# TY_FC_13.net
KiCad netlist of a schematic drawn in EasyEDA Pro
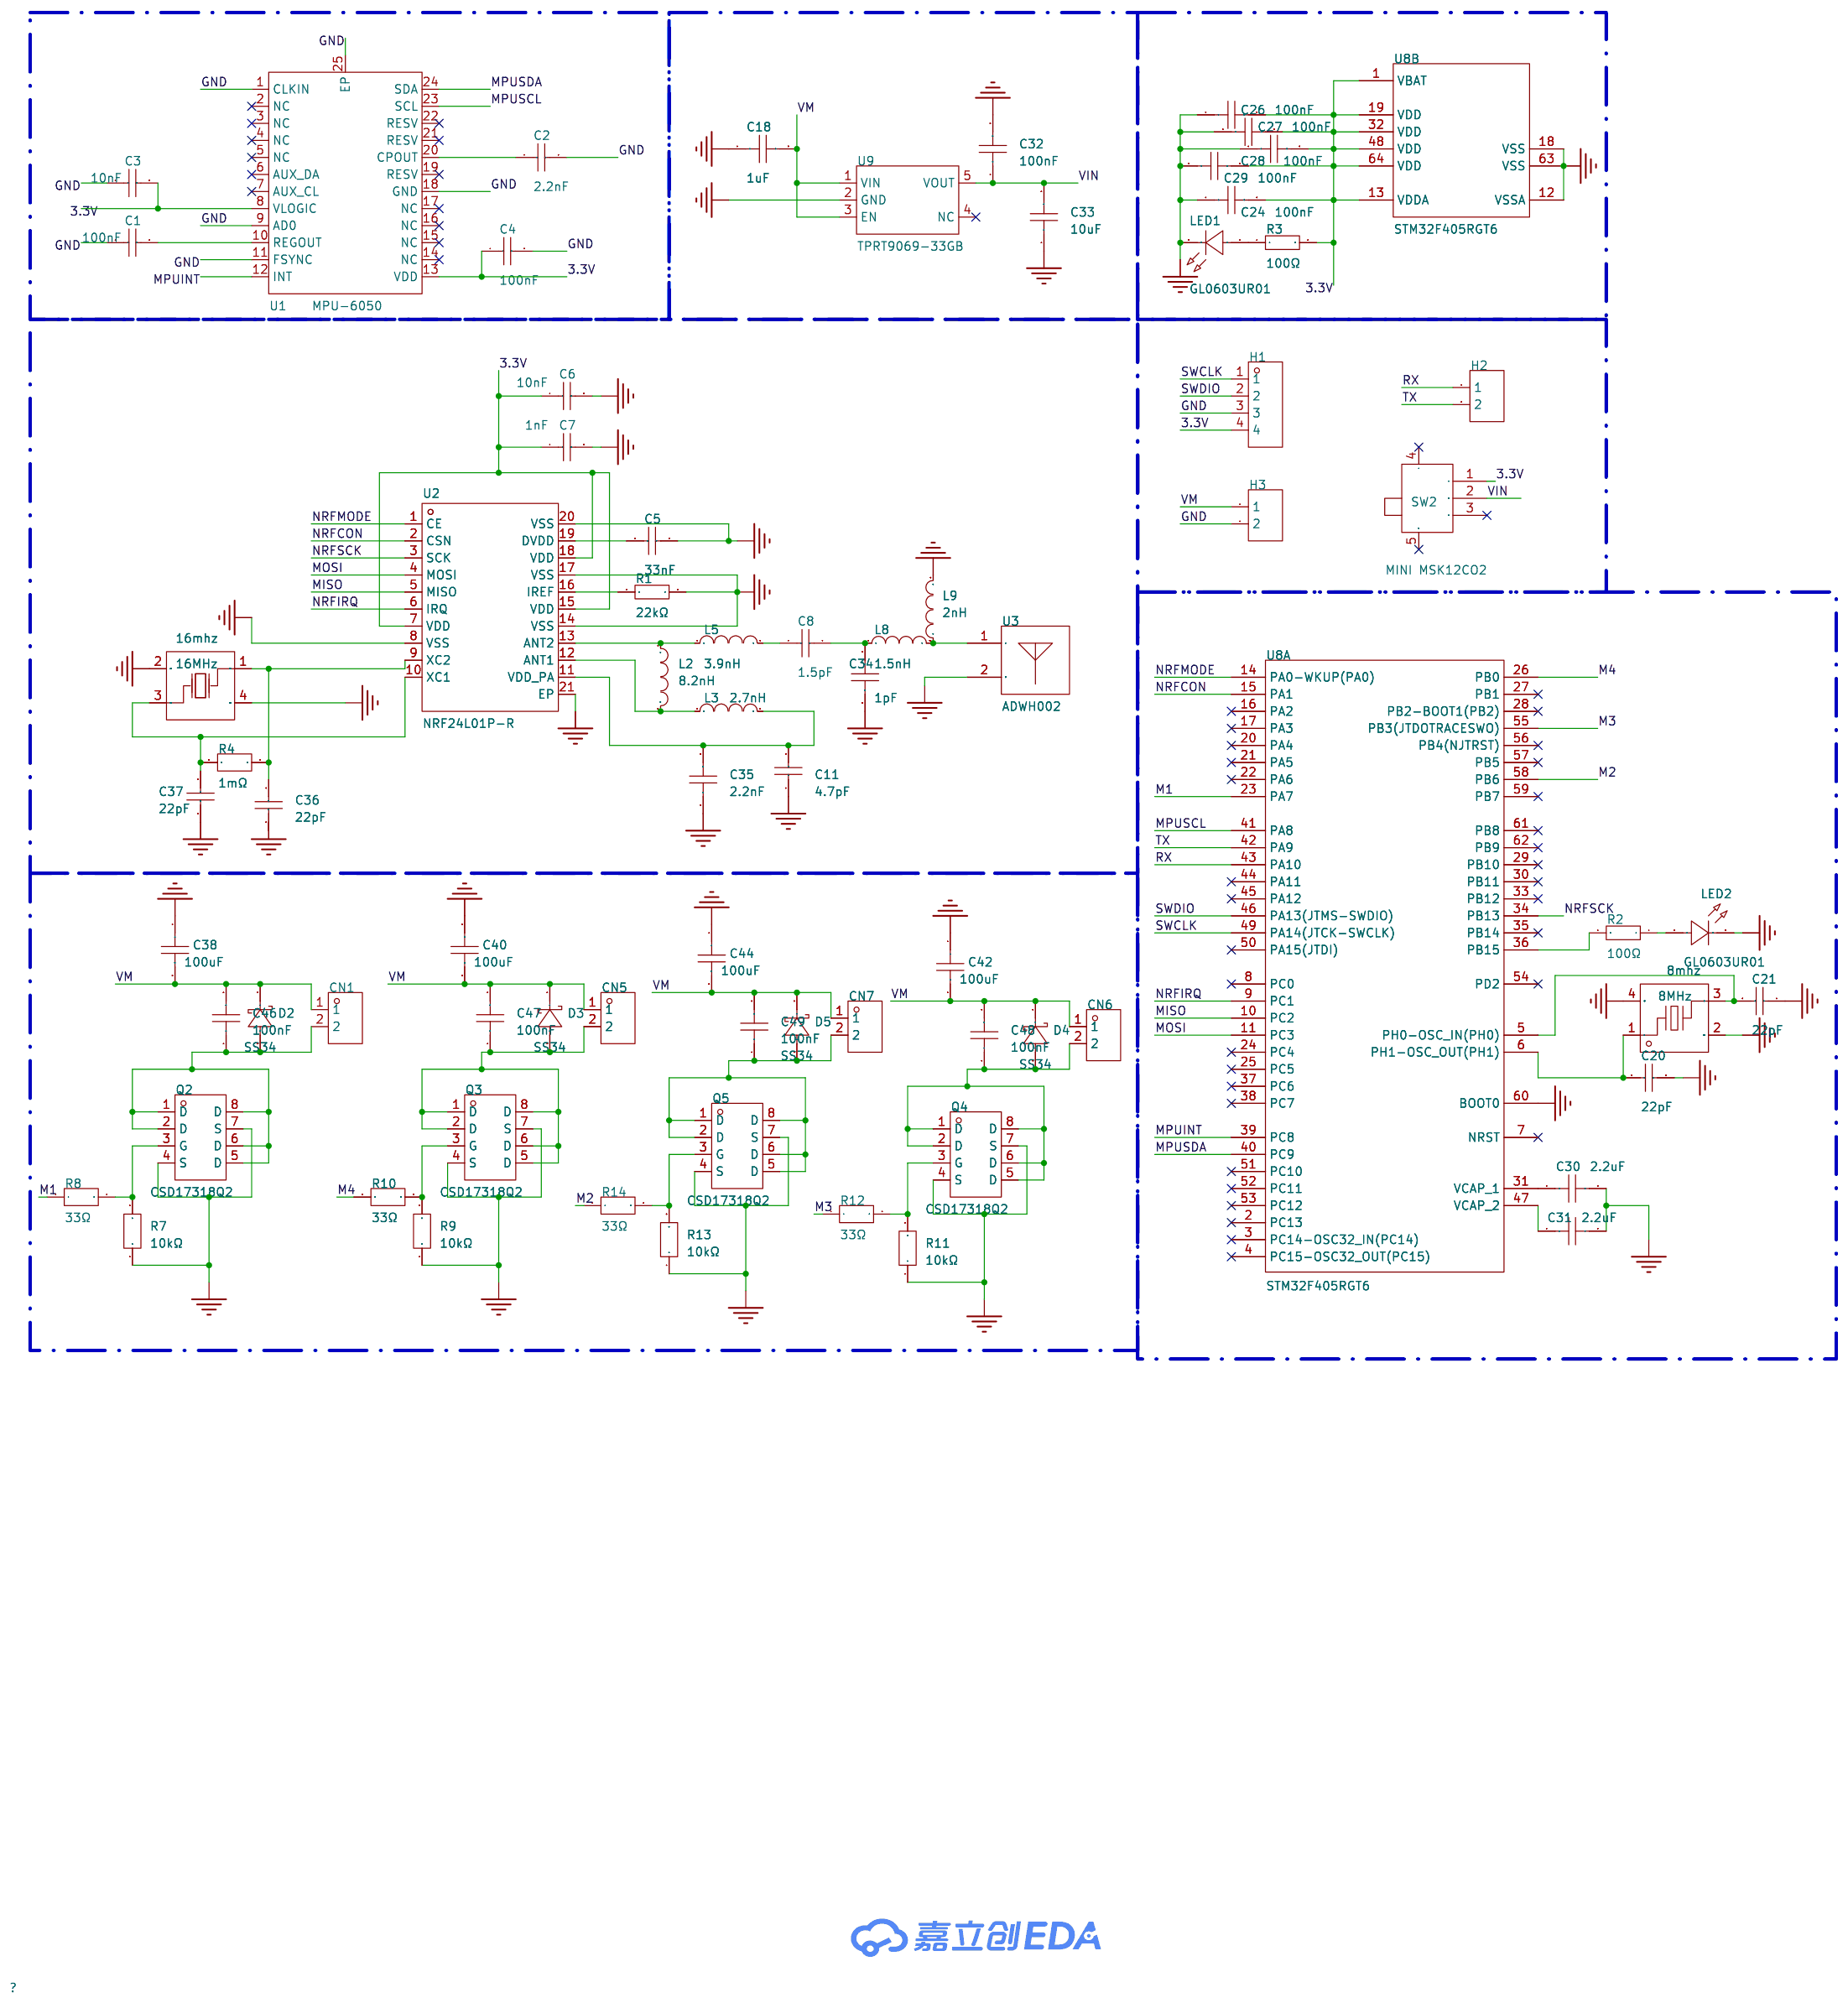
[diagram p0: schematic sheet]

(export (version "E")
  (design (tool "Eeschema 10.0.6"))
  (components
    (comp (ref "8mhz")
      (value "8MHz")
      (footprint "easyedapro:CRYSTAL-SMD_4P-L3.2-W2.5-BL")
      (description "晶振类型:贴片晶振;频率:8MHz;常温频差:±10ppm;负载电容:20pF;频率稳定度:±20ppm;")
      (fields (field (name "Manufacturer Part") "X32258MSB4SI") (field (name "Manufacturer") "YXC(扬兴晶振)"))
      (libsource (lib "easyedapro") (part "X32258MSB4SI"))
    )
    (comp (ref "16mhz")
      (value "16MHz")
      (footprint "easyedapro:OSC-SMD_4P-L3.2-W2.5-BL")
      (description "晶振类型:贴片晶振;频率:16MHz;常温频差:±10ppm;负载电容:9pF;频率稳定度:±20ppm;")
      (fields (field (name "Manufacturer Part") "X322516MLB4SI") (field (name "Manufacturer") "YXC(扬兴晶振)"))
      (libsource (lib "easyedapro") (part "X322516MLB4SI"))
    )
    (comp (ref "C1")
      (value "100nF")
      (footprint "easyedapro:C0805")
      (description "容值:100nF;精度:±10%;额定电压:100V;温度系数:X7R;")
      (fields
        (field (name "Manufacturer Part") "CL21B104KCFNNNE")
        (field (name "Manufacturer") "SAMSUNG(三星)")
      )
      (libsource (lib "easyedapro") (part "CL21B104KCFNNNE"))
    )
    (comp (ref "C2")
      (value "2.2nF")
      (footprint "easyedapro:C0805")
      (description "容值:2.2nF;精度:±5%;额定电压:50V;温度系数:C0G;")
      (fields
        (field (name "Manufacturer Part") "CL21C222JBFNNNE")
        (field (name "Manufacturer") "SAMSUNG(三星)")
      )
      (libsource (lib "easyedapro") (part "CL21C222JBFNNNE"))
    )
    (comp (ref "C3")
      (value "10nF")
      (footprint "easyedapro:C0805")
      (description "容值:10nF;精度:±10%;额定电压:50V;温度系数:X7R;")
      (fields
        (field (name "Manufacturer Part") "CL21B103KBANNNC")
        (field (name "Manufacturer") "SAMSUNG(三星)")
      )
      (libsource (lib "easyedapro") (part "CL21B103KBANNNC"))
    )
    (comp (ref "C4")
      (value "100nF")
      (footprint "easyedapro:C0805")
      (description "容值:100nF;精度:±10%;额定电压:100V;温度系数:X7R;")
      (fields
        (field (name "Manufacturer Part") "CL21B104KCFNNNE")
        (field (name "Manufacturer") "SAMSUNG(三星)")
      )
      (libsource (lib "easyedapro") (part "CL21B104KCFNNNE"))
    )
    (comp (ref "C5")
      (value "33nF")
      (footprint "easyedapro:C0603")
      (description "容值:33nF;精度:±10%;额定电压:50V;温度系数:X7R;")
      (fields
        (field (name "Manufacturer Part") "CL10B333KB8NNNC")
        (field (name "Manufacturer") "SAMSUNG(三星)")
      )
      (libsource (lib "easyedapro") (part "CL10B333KB8NNNC"))
    )
    (comp (ref "C6")
      (value "10nF")
      (footprint "easyedapro:C0603")
      (description "容值:10nF;精度:±10%;额定电压:50V;温度系数:X7R;")
      (fields
        (field (name "Manufacturer Part") "CC0603KRX7R9BB103")
        (field (name "Manufacturer") "YAGEO(国巨)")
      )
      (libsource (lib "easyedapro") (part "CC0603KRX7R9BB103"))
    )
    (comp (ref "C7")
      (value "1nF")
      (footprint "easyedapro:C0603")
      (description "容值:1nF;精度:±10%;额定电压:50V;温度系数:X7R;")
      (fields
        (field (name "Manufacturer Part") "CL10B102KB8NNNC")
        (field (name "Manufacturer") "SAMSUNG(三星)")
      )
      (libsource (lib "easyedapro") (part "CL10B102KB8NNNC"))
    )
    (comp (ref "C8")
      (value "1.5pF")
      (footprint "easyedapro:C0603")
      (description "容值:1.5pF;额定电压:50V;温度系数:C0G;")
      (fields (field (name "Manufacturer Part") "0603CG1R5C500NT") (field (name "Manufacturer") "FH(风华)"))
      (libsource (lib "easyedapro") (part "0603CG1R5C500NT"))
    )
    (comp (ref "C11")
      (value "4.7pF")
      (footprint "easyedapro:C0603")
      (description "容值:4.7pF;额定电压:50V;温度系数:C0G;")
      (fields (field (name "Manufacturer Part") "0603CG4R7C500NT") (field (name "Manufacturer") "FH(风华)"))
      (libsource (lib "easyedapro") (part "0603CG4R7C500NT"))
    )
    (comp (ref "C18")
      (value "1uF")
      (footprint "easyedapro:C0603")
      (description "容值:1uF;精度:±10%;额定电压:50V;温度系数:X5R;")
      (fields
        (field (name "Manufacturer Part") "CGA0603X5R105K500JT")
        (field (name "Manufacturer") "HRE(芯声)")
      )
      (libsource (lib "easyedapro") (part "CGA0603X5R105K500JT"))
    )
    (comp (ref "C20")
      (value "22pF")
      (footprint "easyedapro:C0603")
      (description "容值:22pF;精度:±5%;额定电压:50V;温度系数:C0G;")
      (fields
        (field (name "Manufacturer Part") "CL10C220JB8NNNC")
        (field (name "Manufacturer") "SAMSUNG(三星)")
      )
      (libsource (lib "easyedapro") (part "CL10C220JB8NNNC"))
    )
    (comp (ref "C21")
      (value "22pF")
      (footprint "easyedapro:C0603")
      (description "容值:22pF;精度:±5%;额定电压:50V;温度系数:C0G;")
      (fields
        (field (name "Manufacturer Part") "CL10C220JB8NNNC")
        (field (name "Manufacturer") "SAMSUNG(三星)")
      )
      (libsource (lib "easyedapro") (part "CL10C220JB8NNNC"))
    )
    (comp (ref "C24")
      (value "100nF")
      (footprint "easyedapro:C0603")
      (description "容值:100nF;精度:±10%;额定电压:50V;温度系数:X7R;")
      (fields
        (field (name "Manufacturer Part") "CGA0603X7R104K500JT")
        (field (name "Manufacturer") "HRE(芯声)")
      )
      (libsource (lib "easyedapro") (part "CGA0603X7R104K500JT"))
    )
    (comp (ref "C26")
      (value "100nF")
      (footprint "easyedapro:C0603")
      (description "容值:100nF;精度:±10%;额定电压:50V;温度系数:X7R;")
      (fields
        (field (name "Manufacturer Part") "CGA0603X7R104K500JT")
        (field (name "Manufacturer") "HRE(芯声)")
      )
      (libsource (lib "easyedapro") (part "CGA0603X7R104K500JT"))
    )
    (comp (ref "C27")
      (value "100nF")
      (footprint "easyedapro:C0603")
      (description "容值:100nF;精度:±10%;额定电压:50V;温度系数:X7R;")
      (fields
        (field (name "Manufacturer Part") "CGA0603X7R104K500JT")
        (field (name "Manufacturer") "HRE(芯声)")
      )
      (libsource (lib "easyedapro") (part "CGA0603X7R104K500JT"))
    )
    (comp (ref "C28")
      (value "100nF")
      (footprint "easyedapro:C0603")
      (description "容值:100nF;精度:±10%;额定电压:50V;温度系数:X7R;")
      (fields
        (field (name "Manufacturer Part") "CGA0603X7R104K500JT")
        (field (name "Manufacturer") "HRE(芯声)")
      )
      (libsource (lib "easyedapro") (part "CGA0603X7R104K500JT"))
    )
    (comp (ref "C29")
      (value "100nF")
      (footprint "easyedapro:C0603")
      (description "容值:100nF;精度:±10%;额定电压:50V;温度系数:X7R;")
      (fields
        (field (name "Manufacturer Part") "CGA0603X7R104K500JT")
        (field (name "Manufacturer") "HRE(芯声)")
      )
      (libsource (lib "easyedapro") (part "CGA0603X7R104K500JT"))
    )
    (comp (ref "C30")
      (value "2.2uF")
      (footprint "easyedapro:C0603")
      (description "容值:2.2uF;精度:±10%;额定电压:50V;温度系数:X5R;")
      (fields
        (field (name "Manufacturer Part") "CL10A225KB8NNNC")
        (field (name "Manufacturer") "SAMSUNG(三星)")
      )
      (libsource (lib "easyedapro") (part "CL10A225KB8NNNC"))
    )
    (comp (ref "C31")
      (value "2.2uF")
      (footprint "easyedapro:C0603")
      (description "容值:2.2uF;精度:±10%;额定电压:50V;温度系数:X5R;")
      (fields
        (field (name "Manufacturer Part") "CL10A225KB8NNNC")
        (field (name "Manufacturer") "SAMSUNG(三星)")
      )
      (libsource (lib "easyedapro") (part "CL10A225KB8NNNC"))
    )
    (comp (ref "C32")
      (value "100nF")
      (footprint "easyedapro:C0603")
      (description "容值:100nF;精度:±10%;额定电压:50V;温度系数:X7R;")
      (fields
        (field (name "Manufacturer Part") "CC0603KRX7R9BB104")
        (field (name "Manufacturer") "YAGEO(国巨)")
      )
      (libsource (lib "easyedapro") (part "CC0603KRX7R9BB104"))
    )
    (comp (ref "C33")
      (value "10uF")
      (footprint "easyedapro:C0603")
      (description "容值:10uF;精度:±10%;额定电压:10V;温度系数:X5R;")
      (fields
        (field (name "Manufacturer Part") "CGA0603X5R106K100JT")
        (field (name "Manufacturer") "HRE(芯声)")
      )
      (libsource (lib "easyedapro") (part "CGA0603X5R106K100JT"))
    )
    (comp (ref "C34")
      (value "1pF")
      (footprint "easyedapro:C0603")
      (description "容值:1pF;额定电压:50V;温度系数:C0G;")
      (fields
        (field (name "Manufacturer Part") "CL10C010BB8NNNC")
        (field (name "Manufacturer") "SAMSUNG(三星)")
      )
      (libsource (lib "easyedapro") (part "CL10C010BB8NNNC"))
    )
    (comp (ref "C35")
      (value "2.2nF")
      (footprint "easyedapro:C0603")
      (description "容值:2.2nF;精度:±10%;额定电压:50V;温度系数:X7R;")
      (fields
        (field (name "Manufacturer Part") "FCC0603B222K500CT")
        (field (name "Manufacturer") "FOJAN(富捷)")
      )
      (libsource (lib "easyedapro") (part "FCC0603B222K500CT"))
    )
    (comp (ref "C36")
      (value "22pF")
      (footprint "easyedapro:C0603")
      (description "容值:22pF;精度:±5%;额定电压:50V;温度系数:C0G;")
      (fields
        (field (name "Manufacturer Part") "CL10C220JB8NNNC")
        (field (name "Manufacturer") "SAMSUNG(三星)")
      )
      (libsource (lib "easyedapro") (part "CL10C220JB8NNNC"))
    )
    (comp (ref "C37")
      (value "22pF")
      (footprint "easyedapro:C0603")
      (description "容值:22pF;精度:±5%;额定电压:50V;温度系数:C0G;")
      (fields
        (field (name "Manufacturer Part") "CL10C220JB8NNNC")
        (field (name "Manufacturer") "SAMSUNG(三星)")
      )
      (libsource (lib "easyedapro") (part "CL10C220JB8NNNC"))
    )
    (comp (ref "C38")
      (value "100uF")
      (footprint "easyedapro:C1206")
      (description "容值:100uF;精度:±20%;额定电压:10V;温度系数:X5R;")
      (fields
        (field (name "Manufacturer Part") "HGC1206R5107M100NSPJ")
        (field (name "Manufacturer") "Chinocera(华瓷)")
      )
      (libsource (lib "easyedapro") (part "HGC1206R5107M100NSPJ"))
    )
    (comp (ref "C40")
      (value "100uF")
      (footprint "easyedapro:C1206")
      (description "容值:100uF;精度:±20%;额定电压:10V;温度系数:X5R;")
      (fields
        (field (name "Manufacturer Part") "HGC1206R5107M100NSPJ")
        (field (name "Manufacturer") "Chinocera(华瓷)")
      )
      (libsource (lib "easyedapro") (part "HGC1206R5107M100NSPJ"))
    )
    (comp (ref "C42")
      (value "100uF")
      (footprint "easyedapro:C1206")
      (description "容值:100uF;精度:±20%;额定电压:10V;温度系数:X5R;")
      (fields
        (field (name "Manufacturer Part") "HGC1206R5107M100NSPJ")
        (field (name "Manufacturer") "Chinocera(华瓷)")
      )
      (libsource (lib "easyedapro") (part "HGC1206R5107M100NSPJ"))
    )
    (comp (ref "C44")
      (value "100uF")
      (footprint "easyedapro:C1206")
      (description "容值:100uF;精度:±20%;额定电压:10V;温度系数:X5R;")
      (fields
        (field (name "Manufacturer Part") "HGC1206R5107M100NSPJ")
        (field (name "Manufacturer") "Chinocera(华瓷)")
      )
      (libsource (lib "easyedapro") (part "HGC1206R5107M100NSPJ"))
    )
    (comp (ref "C46")
      (value "100nF")
      (footprint "easyedapro:C0603")
      (description "容值:100nF;精度:±10%;额定电压:50V;温度系数:X7R;")
      (fields
        (field (name "Manufacturer Part") "CGA0603X7R104K500JT")
        (field (name "Manufacturer") "HRE(芯声)")
      )
      (libsource (lib "easyedapro") (part "CGA0603X7R104K500JT"))
    )
    (comp (ref "C47")
      (value "100nF")
      (footprint "easyedapro:C0603")
      (description "容值:100nF;精度:±10%;额定电压:50V;温度系数:X7R;")
      (fields
        (field (name "Manufacturer Part") "CGA0603X7R104K500JT")
        (field (name "Manufacturer") "HRE(芯声)")
      )
      (libsource (lib "easyedapro") (part "CGA0603X7R104K500JT"))
    )
    (comp (ref "C48")
      (value "100nF")
      (footprint "easyedapro:C0603")
      (description "容值:100nF;精度:±10%;额定电压:50V;温度系数:X7R;")
      (fields
        (field (name "Manufacturer Part") "CGA0603X7R104K500JT")
        (field (name "Manufacturer") "HRE(芯声)")
      )
      (libsource (lib "easyedapro") (part "CGA0603X7R104K500JT"))
    )
    (comp (ref "C49")
      (value "100nF")
      (footprint "easyedapro:C0603")
      (description "容值:100nF;精度:±10%;额定电压:50V;温度系数:X7R;")
      (fields
        (field (name "Manufacturer Part") "CGA0603X7R104K500JT")
        (field (name "Manufacturer") "HRE(芯声)")
      )
      (libsource (lib "easyedapro") (part "CGA0603X7R104K500JT"))
    )
    (comp (ref "CN1")
      (value "530480210")
      (footprint "easyedapro:CONN-TH_530480210")
      (fields (field (name "Manufacturer") "MOLEX"))
      (libsource (lib "easyedapro") (part "530480210"))
    )
    (comp (ref "CN5")
      (value "530480210")
      (footprint "easyedapro:CONN-TH_530480210")
      (fields (field (name "Manufacturer") "MOLEX"))
      (libsource (lib "easyedapro") (part "530480210"))
    )
    (comp (ref "CN6")
      (value "530480210")
      (footprint "easyedapro:CONN-TH_530480210")
      (fields (field (name "Manufacturer") "MOLEX"))
      (libsource (lib "easyedapro") (part "530480210"))
    )
    (comp (ref "CN7")
      (value "530480210")
      (footprint "easyedapro:CONN-TH_530480210")
      (fields (field (name "Manufacturer") "MOLEX"))
      (libsource (lib "easyedapro") (part "530480210"))
    )
    (comp (ref "D2")
      (value "SS34")
      (footprint "easyedapro:SMA_L4.3-W2.6-LS5.0-FD")
      (description "二极管配置:独立式;正向压降(Vf):550mV@3A;直流反向耐压(Vr):40V;整流电流:3A;")
      (fields (field (name "Manufacturer") "R+O(宏嘉诚)"))
      (libsource (lib "easyedapro") (part "SS34_C7420365"))
    )
    (comp (ref "D3")
      (value "SS34")
      (footprint "easyedapro:SMA_L4.3-W2.6-LS5.0-FD")
      (description "二极管配置:独立式;正向压降(Vf):550mV@3A;直流反向耐压(Vr):40V;整流电流:3A;")
      (fields (field (name "Manufacturer") "R+O(宏嘉诚)"))
      (libsource (lib "easyedapro") (part "SS34_C7420365"))
    )
    (comp (ref "D4")
      (value "SS34")
      (footprint "easyedapro:SMA_L4.3-W2.6-LS5.0-FD")
      (description "二极管配置:独立式;正向压降(Vf):550mV@3A;直流反向耐压(Vr):40V;整流电流:3A;")
      (fields (field (name "Manufacturer") "R+O(宏嘉诚)"))
      (libsource (lib "easyedapro") (part "SS34_C7420365"))
    )
    (comp (ref "D5")
      (value "SS34")
      (footprint "easyedapro:SMA_L4.3-W2.6-LS5.0-FD")
      (description "二极管配置:独立式;正向压降(Vf):550mV@3A;直流反向耐压(Vr):40V;整流电流:3A;")
      (fields (field (name "Manufacturer") "R+O(宏嘉诚)"))
      (libsource (lib "easyedapro") (part "SS34_C7420365"))
    )
    (comp (ref "H1")
      (value "~")
      (footprint "easyedapro:HDR-TH_4P-P2.54-V-F")
      (libsource (lib "easyedapro") (part "2.54-1*4P母"))
    )
    (comp (ref "H2")
      (value "~")
      (footprint "easyedapro:HDR-TH_2P-P2.54-V-F")
      (libsource (lib "easyedapro") (part "Header-Female-2.54_1x2"))
    )
    (comp (ref "H3")
      (value "~")
      (footprint "easyedapro:HDR-TH_2P-P2.54-V-F")
      (libsource (lib "easyedapro") (part "Header-Female-2.54_1x2"))
    )
    (comp (ref "L2")
      (value "8.2nH")
      (footprint "easyedapro:L0402")
      (description "电感值:8.2nH;精度:±5%;额定电流:300mA;饱和电流(Isat):-;直流电阻(DCR):400mΩ;")
      (fields
        (field (name "Manufacturer Part") "SDCL1005C8N2JTDF")
        (field (name "Manufacturer") "Sunlord(顺络)")
      )
      (libsource (lib "easyedapro") (part "SDCL1005C8N2JTDF"))
    )
    (comp (ref "L3")
      (value "2.7nH")
      (footprint "easyedapro:L0402")
      (description "电感值:2.7nH;精度:-;额定电流:800mA;饱和电流(Isat):-;直流电阻(DCR):120mΩ;")
      (fields (field (name "Manufacturer Part") "LQG15HS2N7S02D") (field (name "Manufacturer") "muRata(村田)"))
      (libsource (lib "easyedapro") (part "LQG15HS2N7S02D"))
    )
    (comp (ref "L5")
      (value "3.9nH")
      (footprint "easyedapro:L0402")
      (description "电感值:3.9nH;精度:-;额定电流:300mA;饱和电流(Isat):-;直流电阻(DCR):200mΩ;")
      (fields
        (field (name "Manufacturer Part") "SDCL1005C3N9STDF")
        (field (name "Manufacturer") "Sunlord(顺络)")
      )
      (libsource (lib "easyedapro") (part "SDCL1005C3N9STDF"))
    )
    (comp (ref "L8")
      (value "1.5nH")
      (footprint "easyedapro:L0603")
      (description "电感值:1.5nH;精度:-;额定电流:1.1A;饱和电流(Isat):-;直流电阻(DCR):100mΩ;")
      (fields (field (name "Manufacturer Part") "LQG18HN1N5S00D") (field (name "Manufacturer") "muRata(村田)"))
      (libsource (lib "easyedapro") (part "LQG18HN1N5S00D"))
    )
    (comp (ref "L9")
      (value "2nH")
      (footprint "easyedapro:L0603")
      (description "电感值:2nH;额定电流:-;饱和电流(Isat):-;直流电阻(DCR):-;")
      (fields
        (field (name "Manufacturer Part") "SDCL1608C2N0STDF")
        (field (name "Manufacturer") "Sunlord(顺络)")
      )
      (libsource (lib "easyedapro") (part "SDCL1608C2N0STDF_C370234"))
    )
    (comp (ref "LED1")
      (value "GL0603UR01")
      (footprint "easyedapro:LED0603-FD")
      (fields (field (name "Manufacturer") "Guiguang light(桂光光电)"))
      (libsource (lib "easyedapro") (part "GL0603UR01"))
    )
    (comp (ref "LED2")
      (value "GL0603UR01")
      (footprint "easyedapro:LED0603-FD")
      (fields (field (name "Manufacturer") "Guiguang light(桂光光电)"))
      (libsource (lib "easyedapro") (part "GL0603UR01"))
    )
    (comp (ref "Q2")
      (value "CSD17318Q2")
      (footprint "easyedapro:WSON-6_L2.0-W2.0-P0.65-TL_CSD19538Q2")
      (description "数量:1个N沟道;漏源电压(Vdss):30V;连续漏极电流(Id):25A;导通电阻(RDS(on)):15.1mΩ@8V,8A;耗散功率(Pd):16W;阈值电压(Vgs(th)):1.2V;")
      (fields (field (name "Manufacturer") "TI(德州仪器)"))
      (libsource (lib "easyedapro") (part "CSD17318Q2"))
    )
    (comp (ref "Q3")
      (value "CSD17318Q2")
      (footprint "easyedapro:WSON-6_L2.0-W2.0-P0.65-TL_CSD19538Q2")
      (description "数量:1个N沟道;漏源电压(Vdss):30V;连续漏极电流(Id):25A;导通电阻(RDS(on)):15.1mΩ@8V,8A;耗散功率(Pd):16W;阈值电压(Vgs(th)):1.2V;")
      (fields (field (name "Manufacturer") "TI(德州仪器)"))
      (libsource (lib "easyedapro") (part "CSD17318Q2"))
    )
    (comp (ref "Q4")
      (value "CSD17318Q2")
      (footprint "easyedapro:WSON-6_L2.0-W2.0-P0.65-TL_CSD19538Q2")
      (description "数量:1个N沟道;漏源电压(Vdss):30V;连续漏极电流(Id):25A;导通电阻(RDS(on)):15.1mΩ@8V,8A;耗散功率(Pd):16W;阈值电压(Vgs(th)):1.2V;")
      (fields (field (name "Manufacturer") "TI(德州仪器)"))
      (libsource (lib "easyedapro") (part "CSD17318Q2"))
    )
    (comp (ref "Q5")
      (value "CSD17318Q2")
      (footprint "easyedapro:WSON-6_L2.0-W2.0-P0.65-TL_CSD19538Q2")
      (description "数量:1个N沟道;漏源电压(Vdss):30V;连续漏极电流(Id):25A;导通电阻(RDS(on)):15.1mΩ@8V,8A;耗散功率(Pd):16W;阈值电压(Vgs(th)):1.2V;")
      (fields (field (name "Manufacturer") "TI(德州仪器)"))
      (libsource (lib "easyedapro") (part "CSD17318Q2"))
    )
    (comp (ref "R1")
      (value "22kΩ")
      (footprint "easyedapro:R0603")
      (description "电阻类型:厚膜电阻;阻值:22kΩ;精度:±1%;功率:100mW;工作电压:75V;温度系数:±100ppm/°C;")
      (fields
        (field (name "Manufacturer Part") "0603WAF2202T5E")
        (field (name "Manufacturer") "UNI-ROYAL(厚声)")
      )
      (libsource (lib "easyedapro") (part "0603WAF2202T5E"))
    )
    (comp (ref "R2")
      (value "100Ω")
      (footprint "easyedapro:R0603")
      (description "电阻类型:厚膜电阻;阻值:100Ω;精度:±1%;功率:100mW;最大工作电压:75V;温度系数:±200ppm/°C;")
      (fields
        (field (name "Manufacturer Part") "0603WAF1000T5E")
        (field (name "Manufacturer") "UNI-ROYAL(厚声)")
      )
      (libsource (lib "easyedapro") (part "0603WAF1000T5E"))
    )
    (comp (ref "R3")
      (value "100Ω")
      (footprint "easyedapro:R0603")
      (description "电阻类型:厚膜电阻;阻值:100Ω;精度:±1%;功率:100mW;最大工作电压:75V;温度系数:±200ppm/°C;")
      (fields
        (field (name "Manufacturer Part") "0603WAF1000T5E")
        (field (name "Manufacturer") "UNI-ROYAL(厚声)")
      )
      (libsource (lib "easyedapro") (part "0603WAF1000T5E"))
    )
    (comp (ref "R4")
      (value "1mΩ")
      (footprint "easyedapro:R0603")
      (description "电阻类型:-;阻值:1mΩ;精度:±1%;功率:100mW;温度系数:±300ppm/°C;")
      (fields
        (field (name "Manufacturer Part") "PA0603FRP070R001L")
        (field (name "Manufacturer") "YAGEO(国巨)")
      )
      (libsource (lib "easyedapro") (part "PA0603FRP070R001L"))
    )
    (comp (ref "R7")
      (value "10kΩ")
      (footprint "easyedapro:R0603")
      (description "电阻类型:厚膜电阻;阻值:10kΩ;精度:±1%;功率:100mW;工作电压:75V;温度系数:±100ppm/°C;")
      (fields (field (name "Manufacturer Part") "FRC0603F1002TS") (field (name "Manufacturer") "FOJAN(富捷)"))
      (libsource (lib "easyedapro") (part "FRC0603F1002TS"))
    )
    (comp (ref "R8")
      (value "33Ω")
      (footprint "easyedapro:R0603")
      (description "电阻类型:厚膜电阻;阻值:33Ω;精度:±1%;功率:100mW;工作电压:75V;温度系数:±100ppm/°C;")
      (fields (field (name "Manufacturer Part") "FRC0603F33R0TS") (field (name "Manufacturer") "FOJAN(富捷)"))
      (libsource (lib "easyedapro") (part "FRC0603F33R0TS"))
    )
    (comp (ref "R9")
      (value "10kΩ")
      (footprint "easyedapro:R0603")
      (description "电阻类型:厚膜电阻;阻值:10kΩ;精度:±1%;功率:100mW;工作电压:75V;温度系数:±100ppm/°C;")
      (fields (field (name "Manufacturer Part") "FRC0603F1002TS") (field (name "Manufacturer") "FOJAN(富捷)"))
      (libsource (lib "easyedapro") (part "FRC0603F1002TS"))
    )
    (comp (ref "R10")
      (value "33Ω")
      (footprint "easyedapro:R0603")
      (description "电阻类型:厚膜电阻;阻值:33Ω;精度:±1%;功率:100mW;工作电压:75V;温度系数:±100ppm/°C;")
      (fields (field (name "Manufacturer Part") "FRC0603F33R0TS") (field (name "Manufacturer") "FOJAN(富捷)"))
      (libsource (lib "easyedapro") (part "FRC0603F33R0TS"))
    )
    (comp (ref "R11")
      (value "10kΩ")
      (footprint "easyedapro:R0603")
      (description "电阻类型:厚膜电阻;阻值:10kΩ;精度:±1%;功率:100mW;工作电压:75V;温度系数:±100ppm/°C;")
      (fields (field (name "Manufacturer Part") "FRC0603F1002TS") (field (name "Manufacturer") "FOJAN(富捷)"))
      (libsource (lib "easyedapro") (part "FRC0603F1002TS"))
    )
    (comp (ref "R12")
      (value "33Ω")
      (footprint "easyedapro:R0603")
      (description "电阻类型:厚膜电阻;阻值:33Ω;精度:±1%;功率:100mW;工作电压:75V;温度系数:±100ppm/°C;")
      (fields (field (name "Manufacturer Part") "FRC0603F33R0TS") (field (name "Manufacturer") "FOJAN(富捷)"))
      (libsource (lib "easyedapro") (part "FRC0603F33R0TS"))
    )
    (comp (ref "R13")
      (value "10kΩ")
      (footprint "easyedapro:R0603")
      (description "电阻类型:厚膜电阻;阻值:10kΩ;精度:±1%;功率:100mW;工作电压:75V;温度系数:±100ppm/°C;")
      (fields (field (name "Manufacturer Part") "FRC0603F1002TS") (field (name "Manufacturer") "FOJAN(富捷)"))
      (libsource (lib "easyedapro") (part "FRC0603F1002TS"))
    )
    (comp (ref "R14")
      (value "33Ω")
      (footprint "easyedapro:R0603")
      (description "电阻类型:厚膜电阻;阻值:33Ω;精度:±1%;功率:100mW;工作电压:75V;温度系数:±100ppm/°C;")
      (fields (field (name "Manufacturer Part") "FRC0603F33R0TS") (field (name "Manufacturer") "FOJAN(富捷)"))
      (libsource (lib "easyedapro") (part "FRC0603F33R0TS"))
    )
    (comp (ref "SW2")
      (value "MINI MSK12CO2")
      (footprint "easyedapro:SW-SMD_MSK12CO2")
      (description "电路结构:单刀双掷;安装方式:卧贴;开关颜色:白色;额定电流:50mA;额定电压:12V;工作寿命:1万次;")
      (fields (field (name "Manufacturer") "SHOU HAN(首韩)"))
      (libsource (lib "easyedapro") (part "MINI MSK12CO2"))
    )
    (comp (ref "U1")
      (value "MPU-6050")
      (footprint "easyedapro:QFN-24_L4.0-W4.0-P0.50-BL-EP2.7")
      (description "传感器类型:加速度计陀螺仪;")
      (fields (field (name "Manufacturer") "TDK InvenSense(应美盛)"))
      (libsource (lib "easyedapro") (part "MPU-6050_C24112"))
    )
    (comp (ref "U2")
      (value "NRF24L01P-R")
      (footprint "easyedapro:QFN-20_L4.0-W4.0-P0.50-BL-EP")
      (description "频率范围:2.4GHz~2.525GHz;接口类型:SPI;应用领域:ISM;数据速率:2Mbps;灵敏度:-82dBm;典型应用频率:2.4GHz;")
      (fields (field (name "Manufacturer") "NORDIC"))
      (libsource (lib "easyedapro") (part "NRF24L01P-R"))
    )
    (comp (ref "U3")
      (value "ADWH002")
      (footprint "easyedapro:ANT-SMD_L5.0-W2.0_HM5B")
      (description "天线类型:-;中心频率:2.45GHz;带宽:100MHz;增益:0.67dBi;功率:3W;驻波比:2;")
      (fields (field (name "Manufacturer") "MyAntenna(摩天射频)"))
      (libsource (lib "easyedapro") (part "ADWH002"))
    )
    (comp (ref "U8")
      (value "STM32F405RGT6")
      (footprint "easyedapro:LQFP-64_L10.0-W10.0-P0.50-LS12.0-BL")
      (description "CPU内核:ARM-M4;CPU最大主频:168MHz;应用领域:-;")
      (fields (field (name "Manufacturer") "ST(意法半导体)"))
      (libsource (lib "easyedapro") (part "STM32F405RGT6"))
    )
    (comp (ref "U9")
      (value "TPRT9069-33GB")
      (footprint "easyedapro:SOT-23-5_L3.0-W1.7-P0.95-LS2.8-BR")
      (description "输出类型:固定;工作电压:36V;输出电压:3.3V;输出电流:200mA;电源纹波抑制比(PSRR):70dB@(100Hz);输出极性:正极;")
      (fields (field (name "Manufacturer") "TECH PUBLIC(台舟)"))
      (libsource (lib "easyedapro") (part "TPRT9069-33GB"))
    )
  )
  (nets
    (net (code "1") (name "/3.3V") (class "Default")
      (node (ref "C24") (pin "2") (pinfunction "2_2") (pintype "unspecified"))
      (node (ref "C26") (pin "2") (pinfunction "2_2") (pintype "unspecified"))
      (node (ref "C27") (pin "2") (pinfunction "2_2") (pintype "unspecified"))
      (node (ref "C28") (pin "2") (pinfunction "2_2") (pintype "unspecified"))
      (node (ref "C29") (pin "2") (pinfunction "2_2") (pintype "unspecified"))
      (node (ref "C3") (pin "2") (pinfunction "2_2") (pintype "input"))
      (node (ref "C4") (pin "1") (pinfunction "1_1") (pintype "input"))
      (node (ref "C6") (pin "1") (pinfunction "1_1") (pintype "input"))
      (node (ref "C7") (pin "1") (pinfunction "1_1") (pintype "input"))
      (node (ref "H1") (pin "4") (pinfunction "4_4") (pintype "unspecified"))
      (node (ref "R3") (pin "2") (pinfunction "2_2") (pintype "input"))
      (node (ref "SW2") (pin "1") (pinfunction "1_1") (pintype "unspecified"))
      (node (ref "U1") (pin "13") (pinfunction "VDD_13") (pintype "unspecified"))
      (node (ref "U1") (pin "8") (pinfunction "VLOGIC_8") (pintype "unspecified"))
      (node (ref "U2") (pin "15") (pinfunction "VDD_15") (pintype "unspecified"))
      (node (ref "U2") (pin "18") (pinfunction "VDD_18") (pintype "unspecified"))
      (node (ref "U2") (pin "7") (pinfunction "VDD_7") (pintype "unspecified"))
      (node (ref "U8") (pin "1") (pinfunction "VBAT_1") (pintype "unspecified"))
      (node (ref "U8") (pin "13") (pinfunction "VDDA_13") (pintype "unspecified"))
      (node (ref "U8") (pin "19") (pinfunction "VDD_19") (pintype "unspecified"))
      (node (ref "U8") (pin "32") (pinfunction "VDD_32") (pintype "unspecified"))
      (node (ref "U8") (pin "48") (pinfunction "VDD_48") (pintype "unspecified"))
      (node (ref "U8") (pin "64") (pinfunction "VDD_64") (pintype "unspecified"))
    )
    (net (code "2") (name "/M1") (class "Default")
      (node (ref "R8") (pin "1") (pinfunction "1_1") (pintype "unspecified"))
      (node (ref "U8") (pin "23") (pinfunction "PA7_23") (pintype "bidirectional"))
    )
    (net (code "3") (name "/M2") (class "Default")
      (node (ref "R14") (pin "1") (pinfunction "1_1") (pintype "unspecified"))
      (node (ref "U8") (pin "58") (pinfunction "PB6_58") (pintype "bidirectional"))
    )
    (net (code "4") (name "/M3") (class "Default")
      (node (ref "R12") (pin "1") (pinfunction "1_1") (pintype "unspecified"))
      (node (ref "U8") (pin "55") (pinfunction "PB3(JTDOTRACESWO)_55") (pintype "bidirectional"))
    )
    (net (code "5") (name "/M4") (class "Default")
      (node (ref "R10") (pin "1") (pinfunction "1_1") (pintype "unspecified"))
      (node (ref "U8") (pin "26") (pinfunction "PB0_26") (pintype "bidirectional"))
    )
    (net (code "6") (name "/MISO") (class "Default")
      (node (ref "U2") (pin "5") (pinfunction "MISO_5") (pintype "unspecified"))
      (node (ref "U8") (pin "10") (pinfunction "PC2_10") (pintype "bidirectional"))
    )
    (net (code "7") (name "/MOSI") (class "Default")
      (node (ref "U2") (pin "4") (pinfunction "MOSI_4") (pintype "unspecified"))
      (node (ref "U8") (pin "11") (pinfunction "PC3_11") (pintype "bidirectional"))
    )
    (net (code "8") (name "/MPUINT") (class "Default")
      (node (ref "U1") (pin "12") (pinfunction "INT_12") (pintype "unspecified"))
      (node (ref "U8") (pin "39") (pinfunction "PC8_39") (pintype "bidirectional"))
    )
    (net (code "9") (name "/MPUSCL") (class "Default")
      (node (ref "U1") (pin "23") (pinfunction "SCL_23") (pintype "unspecified"))
      (node (ref "U8") (pin "41") (pinfunction "PA8_41") (pintype "bidirectional"))
    )
    (net (code "10") (name "/MPUSDA") (class "Default")
      (node (ref "U1") (pin "24") (pinfunction "SDA_24") (pintype "unspecified"))
      (node (ref "U8") (pin "40") (pinfunction "PC9_40") (pintype "bidirectional"))
    )
    (net (code "11") (name "/NRFCON") (class "Default")
      (node (ref "U2") (pin "2") (pinfunction "CSN_2") (pintype "unspecified"))
      (node (ref "U8") (pin "15") (pinfunction "PA1_15") (pintype "bidirectional"))
    )
    (net (code "12") (name "/NRFIRQ") (class "Default")
      (node (ref "U2") (pin "6") (pinfunction "IRQ_6") (pintype "unspecified"))
      (node (ref "U8") (pin "9") (pinfunction "PC1_9") (pintype "bidirectional"))
    )
    (net (code "13") (name "/NRFMODE") (class "Default")
      (node (ref "U2") (pin "1") (pinfunction "CE_1") (pintype "unspecified"))
      (node (ref "U8") (pin "14") (pinfunction "PA0-WKUP(PA0)_14") (pintype "bidirectional"))
    )
    (net (code "14") (name "/NRFSCK") (class "Default")
      (node (ref "U2") (pin "3") (pinfunction "SCK_3") (pintype "unspecified"))
      (node (ref "U8") (pin "34") (pinfunction "PB13_34") (pintype "bidirectional"))
    )
    (net (code "15") (name "/RX") (class "Default")
      (node (ref "H2") (pin "1") (pinfunction "1_1") (pintype "input"))
      (node (ref "U8") (pin "43") (pinfunction "PA10_43") (pintype "bidirectional"))
    )
    (net (code "16") (name "/SWCLK") (class "Default")
      (node (ref "H1") (pin "1") (pinfunction "1_1") (pintype "unspecified"))
      (node (ref "U8") (pin "49") (pinfunction "PA14(JTCK-SWCLK)_49") (pintype "bidirectional"))
    )
    (net (code "17") (name "/SWDIO") (class "Default")
      (node (ref "H1") (pin "2") (pinfunction "2_2") (pintype "unspecified"))
      (node (ref "U8") (pin "46") (pinfunction "PA13(JTMS-SWDIO)_46") (pintype "bidirectional"))
    )
    (net (code "18") (name "/TX") (class "Default")
      (node (ref "H2") (pin "2") (pinfunction "2_2") (pintype "input"))
      (node (ref "U8") (pin "42") (pinfunction "PA9_42") (pintype "bidirectional"))
    )
    (net (code "19") (name "/VIN") (class "Default")
      (node (ref "C32") (pin "1") (pinfunction "1_1") (pintype "unspecified"))
      (node (ref "C33") (pin "2") (pinfunction "2_2") (pintype "unspecified"))
      (node (ref "SW2") (pin "2") (pinfunction "2_2") (pintype "unspecified"))
      (node (ref "U9") (pin "5") (pinfunction "VOUT_5") (pintype "unspecified"))
    )
    (net (code "20") (name "/VM") (class "Default")
      (node (ref "C18") (pin "2") (pinfunction "2_2") (pintype "unspecified"))
      (node (ref "C38") (pin "2") (pinfunction "2_2") (pintype "unspecified"))
      (node (ref "C40") (pin "2") (pinfunction "2_2") (pintype "unspecified"))
      (node (ref "C42") (pin "2") (pinfunction "2_2") (pintype "unspecified"))
      (node (ref "C44") (pin "2") (pinfunction "2_2") (pintype "unspecified"))
      (node (ref "C46") (pin "2") (pinfunction "2_2") (pintype "unspecified"))
      (node (ref "C47") (pin "2") (pinfunction "2_2") (pintype "unspecified"))
      (node (ref "C48") (pin "2") (pinfunction "2_2") (pintype "unspecified"))
      (node (ref "C49") (pin "2") (pinfunction "2_2") (pintype "unspecified"))
      (node (ref "CN1") (pin "1") (pinfunction "1_1") (pintype "unspecified"))
      (node (ref "CN5") (pin "1") (pinfunction "1_1") (pintype "unspecified"))
      (node (ref "CN6") (pin "1") (pinfunction "1_1") (pintype "unspecified"))
      (node (ref "CN7") (pin "1") (pinfunction "1_1") (pintype "unspecified"))
      (node (ref "D2") (pin "2") (pinfunction "K_2") (pintype "unspecified"))
      (node (ref "D3") (pin "2") (pinfunction "K_2") (pintype "unspecified"))
      (node (ref "D4") (pin "2") (pinfunction "K_2") (pintype "unspecified"))
      (node (ref "D5") (pin "2") (pinfunction "K_2") (pintype "unspecified"))
      (node (ref "H3") (pin "1") (pinfunction "1_1") (pintype "input"))
      (node (ref "U9") (pin "1") (pinfunction "VIN_1") (pintype "unspecified"))
      (node (ref "U9") (pin "3") (pinfunction "EN_3") (pintype "unspecified"))
    )
    (net (code "21") (name "GND") (class "Default")
      (node (ref "16mhz") (pin "2") (pinfunction "GND_2") (pintype "unspecified"))
      (node (ref "16mhz") (pin "4") (pinfunction "GND_4") (pintype "unspecified"))
      (node (ref "8mhz") (pin "2") (pinfunction "GND_2") (pintype "input"))
      (node (ref "8mhz") (pin "4") (pinfunction "GND_4") (pintype "input"))
      (node (ref "C1") (pin "1") (pinfunction "1_1") (pintype "input"))
      (node (ref "C11") (pin "1") (pinfunction "1_1") (pintype "input"))
      (node (ref "C18") (pin "1") (pinfunction "1_1") (pintype "unspecified"))
      (node (ref "C2") (pin "2") (pinfunction "2_2") (pintype "input"))
      (node (ref "C20") (pin "2") (pinfunction "2_2") (pintype "input"))
      (node (ref "C21") (pin "1") (pinfunction "1_1") (pintype "input"))
      (node (ref "C24") (pin "1") (pinfunction "1_1") (pintype "unspecified"))
      (node (ref "C26") (pin "1") (pinfunction "1_1") (pintype "unspecified"))
      (node (ref "C27") (pin "1") (pinfunction "1_1") (pintype "unspecified"))
      (node (ref "C28") (pin "1") (pinfunction "1_1") (pintype "unspecified"))
      (node (ref "C29") (pin "1") (pinfunction "1_1") (pintype "unspecified"))
      (node (ref "C3") (pin "1") (pinfunction "1_1") (pintype "input"))
      (node (ref "C30") (pin "2") (pinfunction "2_2") (pintype "unspecified"))
      (node (ref "C31") (pin "2") (pinfunction "2_2") (pintype "unspecified"))
      (node (ref "C32") (pin "2") (pinfunction "2_2") (pintype "unspecified"))
      (node (ref "C33") (pin "1") (pinfunction "1_1") (pintype "unspecified"))
      (node (ref "C34") (pin "2") (pinfunction "2_2") (pintype "unspecified"))
      (node (ref "C35") (pin "1") (pinfunction "1_1") (pintype "unspecified"))
      (node (ref "C36") (pin "1") (pinfunction "1_1") (pintype "input"))
      (node (ref "C37") (pin "1") (pinfunction "1_1") (pintype "input"))
      (node (ref "C38") (pin "1") (pinfunction "1_1") (pintype "unspecified"))
      (node (ref "C4") (pin "2") (pinfunction "2_2") (pintype "input"))
      (node (ref "C40") (pin "1") (pinfunction "1_1") (pintype "unspecified"))
      (node (ref "C42") (pin "1") (pinfunction "1_1") (pintype "unspecified"))
      (node (ref "C44") (pin "1") (pinfunction "1_1") (pintype "unspecified"))
      (node (ref "C5") (pin "2") (pinfunction "2_2") (pintype "input"))
      (node (ref "C6") (pin "2") (pinfunction "2_2") (pintype "input"))
      (node (ref "C7") (pin "2") (pinfunction "2_2") (pintype "input"))
      (node (ref "H1") (pin "3") (pinfunction "3_3") (pintype "unspecified"))
      (node (ref "H3") (pin "2") (pinfunction "2_2") (pintype "input"))
      (node (ref "L9") (pin "2") (pinfunction "2_2") (pintype "unspecified"))
      (node (ref "LED1") (pin "2") (pinfunction "C_2") (pintype "unspecified"))
      (node (ref "LED2") (pin "2") (pinfunction "C_2") (pintype "unspecified"))
      (node (ref "Q2") (pin "4") (pinfunction "S_4") (pintype "unspecified"))
      (node (ref "Q2") (pin "7") (pinfunction "S_7") (pintype "unspecified"))
      (node (ref "Q3") (pin "4") (pinfunction "S_4") (pintype "unspecified"))
      (node (ref "Q3") (pin "7") (pinfunction "S_7") (pintype "unspecified"))
      (node (ref "Q4") (pin "4") (pinfunction "S_4") (pintype "unspecified"))
      (node (ref "Q4") (pin "7") (pinfunction "S_7") (pintype "unspecified"))
      (node (ref "Q5") (pin "4") (pinfunction "S_4") (pintype "unspecified"))
      (node (ref "Q5") (pin "7") (pinfunction "S_7") (pintype "unspecified"))
      (node (ref "R1") (pin "2") (pinfunction "2_2") (pintype "input"))
      (node (ref "R11") (pin "1") (pinfunction "1_1") (pintype "unspecified"))
      (node (ref "R13") (pin "1") (pinfunction "1_1") (pintype "unspecified"))
      (node (ref "R7") (pin "1") (pinfunction "1_1") (pintype "unspecified"))
      (node (ref "R9") (pin "1") (pinfunction "1_1") (pintype "unspecified"))
      (node (ref "U1") (pin "1") (pinfunction "CLKIN_1") (pintype "unspecified"))
      (node (ref "U1") (pin "11") (pinfunction "FSYNC_11") (pintype "unspecified"))
      (node (ref "U1") (pin "18") (pinfunction "GND_18") (pintype "unspecified"))
      (node (ref "U1") (pin "25") (pinfunction "EP_25") (pintype "unspecified"))
      (node (ref "U1") (pin "9") (pinfunction "AD0_9") (pintype "unspecified"))
      (node (ref "U2") (pin "14") (pinfunction "VSS_14") (pintype "unspecified"))
      (node (ref "U2") (pin "17") (pinfunction "VSS_17") (pintype "unspecified"))
      (node (ref "U2") (pin "20") (pinfunction "VSS_20") (pintype "unspecified"))
      (node (ref "U2") (pin "21") (pinfunction "EP_21") (pintype "unspecified"))
      (node (ref "U2") (pin "8") (pinfunction "VSS_8") (pintype "unspecified"))
      (node (ref "U3") (pin "2") (pinfunction "GND_2") (pintype "unspecified"))
      (node (ref "U8") (pin "12") (pinfunction "VSSA_12") (pintype "unspecified"))
      (node (ref "U8") (pin "18") (pinfunction "VSS_18") (pintype "unspecified"))
      (node (ref "U8") (pin "60") (pinfunction "BOOT0_60") (pintype "unspecified"))
      (node (ref "U8") (pin "63") (pinfunction "VSS_63") (pintype "unspecified"))
      (node (ref "U9") (pin "2") (pinfunction "GND_2") (pintype "unspecified"))
    )
    (net (code "22") (name "Net-(16mhz-OSC1)") (class "Default")
      (node (ref "16mhz") (pin "1") (pinfunction "OSC1_1") (pintype "unspecified"))
      (node (ref "C36") (pin "2") (pinfunction "2_2") (pintype "input"))
      (node (ref "R4") (pin "1") (pinfunction "1_1") (pintype "unspecified"))
      (node (ref "U2") (pin "9") (pinfunction "XC2_9") (pintype "unspecified"))
    )
    (net (code "23") (name "Net-(16mhz-OSC2)") (class "Default")
      (node (ref "16mhz") (pin "3") (pinfunction "OSC2_3") (pintype "unspecified"))
      (node (ref "C37") (pin "2") (pinfunction "2_2") (pintype "input"))
      (node (ref "R4") (pin "2") (pinfunction "2_2") (pintype "unspecified"))
      (node (ref "U2") (pin "10") (pinfunction "XC1_10") (pintype "unspecified"))
    )
    (net (code "24") (name "Net-(C8-Pad1)") (class "Default")
      (node (ref "C8") (pin "1") (pinfunction "1_1") (pintype "input"))
      (node (ref "L5") (pin "2") (pinfunction "2_2") (pintype "unspecified"))
    )
    (net (code "25") (name "Net-(C34-Pad1)") (class "Default")
      (node (ref "C34") (pin "1") (pinfunction "1_1") (pintype "unspecified"))
      (node (ref "C8") (pin "2") (pinfunction "2_2") (pintype "input"))
      (node (ref "L8") (pin "1") (pinfunction "1_1") (pintype "unspecified"))
    )
    (net (code "26") (name "Net-(D2-A)") (class "Default")
      (node (ref "C46") (pin "1") (pinfunction "1_1") (pintype "unspecified"))
      (node (ref "CN1") (pin "2") (pinfunction "2_2") (pintype "unspecified"))
      (node (ref "D2") (pin "1") (pinfunction "A_1") (pintype "unspecified"))
      (node (ref "Q2") (pin "1") (pinfunction "D_1") (pintype "unspecified"))
      (node (ref "Q2") (pin "2") (pinfunction "D_2") (pintype "unspecified"))
      (node (ref "Q2") (pin "5") (pinfunction "D_5") (pintype "unspecified"))
      (node (ref "Q2") (pin "6") (pinfunction "D_6") (pintype "unspecified"))
      (node (ref "Q2") (pin "8") (pinfunction "D_8") (pintype "unspecified"))
    )
    (net (code "27") (name "Net-(D3-A)") (class "Default")
      (node (ref "C47") (pin "1") (pinfunction "1_1") (pintype "unspecified"))
      (node (ref "CN5") (pin "2") (pinfunction "2_2") (pintype "unspecified"))
      (node (ref "D3") (pin "1") (pinfunction "A_1") (pintype "unspecified"))
      (node (ref "Q3") (pin "1") (pinfunction "D_1") (pintype "unspecified"))
      (node (ref "Q3") (pin "2") (pinfunction "D_2") (pintype "unspecified"))
      (node (ref "Q3") (pin "5") (pinfunction "D_5") (pintype "unspecified"))
      (node (ref "Q3") (pin "6") (pinfunction "D_6") (pintype "unspecified"))
      (node (ref "Q3") (pin "8") (pinfunction "D_8") (pintype "unspecified"))
    )
    (net (code "28") (name "Net-(D4-A)") (class "Default")
      (node (ref "C48") (pin "1") (pinfunction "1_1") (pintype "unspecified"))
      (node (ref "CN6") (pin "2") (pinfunction "2_2") (pintype "unspecified"))
      (node (ref "D4") (pin "1") (pinfunction "A_1") (pintype "unspecified"))
      (node (ref "Q4") (pin "1") (pinfunction "D_1") (pintype "unspecified"))
      (node (ref "Q4") (pin "2") (pinfunction "D_2") (pintype "unspecified"))
      (node (ref "Q4") (pin "5") (pinfunction "D_5") (pintype "unspecified"))
      (node (ref "Q4") (pin "6") (pinfunction "D_6") (pintype "unspecified"))
      (node (ref "Q4") (pin "8") (pinfunction "D_8") (pintype "unspecified"))
    )
    (net (code "29") (name "Net-(D5-A)") (class "Default")
      (node (ref "C49") (pin "1") (pinfunction "1_1") (pintype "unspecified"))
      (node (ref "CN7") (pin "2") (pinfunction "2_2") (pintype "unspecified"))
      (node (ref "D5") (pin "1") (pinfunction "A_1") (pintype "unspecified"))
      (node (ref "Q5") (pin "1") (pinfunction "D_1") (pintype "unspecified"))
      (node (ref "Q5") (pin "2") (pinfunction "D_2") (pintype "unspecified"))
      (node (ref "Q5") (pin "5") (pinfunction "D_5") (pintype "unspecified"))
      (node (ref "Q5") (pin "6") (pinfunction "D_6") (pintype "unspecified"))
      (node (ref "Q5") (pin "8") (pinfunction "D_8") (pintype "unspecified"))
    )
    (net (code "30") (name "Net-(LED1-A)") (class "Default")
      (node (ref "LED1") (pin "1") (pinfunction "A_1") (pintype "unspecified"))
      (node (ref "R3") (pin "1") (pinfunction "1_1") (pintype "input"))
    )
    (net (code "31") (name "Net-(LED2-A)") (class "Default")
      (node (ref "LED2") (pin "1") (pinfunction "A_1") (pintype "unspecified"))
      (node (ref "R2") (pin "1") (pinfunction "1_1") (pintype "input"))
    )
    (net (code "32") (name "Net-(Q2-G)") (class "Default")
      (node (ref "Q2") (pin "3") (pinfunction "G_3") (pintype "unspecified"))
      (node (ref "R7") (pin "2") (pinfunction "2_2") (pintype "unspecified"))
      (node (ref "R8") (pin "2") (pinfunction "2_2") (pintype "unspecified"))
    )
    (net (code "33") (name "Net-(Q3-G)") (class "Default")
      (node (ref "Q3") (pin "3") (pinfunction "G_3") (pintype "unspecified"))
      (node (ref "R10") (pin "2") (pinfunction "2_2") (pintype "unspecified"))
      (node (ref "R9") (pin "2") (pinfunction "2_2") (pintype "unspecified"))
    )
    (net (code "34") (name "Net-(Q4-G)") (class "Default")
      (node (ref "Q4") (pin "3") (pinfunction "G_3") (pintype "unspecified"))
      (node (ref "R11") (pin "2") (pinfunction "2_2") (pintype "unspecified"))
      (node (ref "R12") (pin "2") (pinfunction "2_2") (pintype "unspecified"))
    )
    (net (code "35") (name "Net-(Q5-G)") (class "Default")
      (node (ref "Q5") (pin "3") (pinfunction "G_3") (pintype "unspecified"))
      (node (ref "R13") (pin "2") (pinfunction "2_2") (pintype "unspecified"))
      (node (ref "R14") (pin "2") (pinfunction "2_2") (pintype "unspecified"))
    )
    (net (code "36") (name "Net-(U1-CPOUT)") (class "Default")
      (node (ref "C2") (pin "1") (pinfunction "1_1") (pintype "input"))
      (node (ref "U1") (pin "20") (pinfunction "CPOUT_20") (pintype "unspecified"))
    )
    (net (code "37") (name "Net-(U1-REGOUT)") (class "Default")
      (node (ref "C1") (pin "2") (pinfunction "2_2") (pintype "input"))
      (node (ref "U1") (pin "10") (pinfunction "REGOUT_10") (pintype "unspecified"))
    )
    (net (code "38") (name "Net-(U2-ANT1)") (class "Default")
      (node (ref "L2") (pin "2") (pinfunction "2_2") (pintype "unspecified"))
      (node (ref "L3") (pin "1") (pinfunction "1_1") (pintype "unspecified"))
      (node (ref "U2") (pin "12") (pinfunction "ANT1_12") (pintype "unspecified"))
    )
    (net (code "39") (name "Net-(U2-ANT2)") (class "Default")
      (node (ref "L2") (pin "1") (pinfunction "1_1") (pintype "unspecified"))
      (node (ref "L5") (pin "1") (pinfunction "1_1") (pintype "unspecified"))
      (node (ref "U2") (pin "13") (pinfunction "ANT2_13") (pintype "unspecified"))
    )
    (net (code "40") (name "Net-(U2-DVDD)") (class "Default")
      (node (ref "C5") (pin "1") (pinfunction "1_1") (pintype "input"))
      (node (ref "U2") (pin "19") (pinfunction "DVDD_19") (pintype "unspecified"))
    )
    (net (code "41") (name "Net-(U2-IREF)") (class "Default")
      (node (ref "R1") (pin "1") (pinfunction "1_1") (pintype "input"))
      (node (ref "U2") (pin "16") (pinfunction "IREF_16") (pintype "unspecified"))
    )
    (net (code "42") (name "Net-(U2-VDD_PA)") (class "Default")
      (node (ref "C11") (pin "2") (pinfunction "2_2") (pintype "input"))
      (node (ref "C35") (pin "2") (pinfunction "2_2") (pintype "unspecified"))
      (node (ref "L3") (pin "2") (pinfunction "2_2") (pintype "unspecified"))
      (node (ref "U2") (pin "11") (pinfunction "VDD_PA_11") (pintype "unspecified"))
    )
    (net (code "43") (name "Net-(U3-IN)") (class "Default")
      (node (ref "L8") (pin "2") (pinfunction "2_2") (pintype "unspecified"))
      (node (ref "L9") (pin "1") (pinfunction "1_1") (pintype "unspecified"))
      (node (ref "U3") (pin "1") (pinfunction "IN_1") (pintype "unspecified"))
    )
    (net (code "44") (name "Net-(U8A-PB15)") (class "Default")
      (node (ref "R2") (pin "2") (pinfunction "2_2") (pintype "input"))
      (node (ref "U8") (pin "36") (pinfunction "PB15_36") (pintype "bidirectional"))
    )
    (net (code "45") (name "Net-(U8A-PH0-OSC_IN(PH0))") (class "Default")
      (node (ref "8mhz") (pin "3") (pinfunction "3_3") (pintype "input"))
      (node (ref "C21") (pin "2") (pinfunction "2_2") (pintype "input"))
      (node (ref "U8") (pin "5") (pinfunction "PH0-OSC_IN(PH0)_5") (pintype "bidirectional"))
    )
    (net (code "46") (name "Net-(U8A-PH1-OSC_OUT(PH1))") (class "Default")
      (node (ref "8mhz") (pin "1") (pinfunction "1_1") (pintype "input"))
      (node (ref "C20") (pin "1") (pinfunction "1_1") (pintype "input"))
      (node (ref "U8") (pin "6") (pinfunction "PH1-OSC_OUT(PH1)_6") (pintype "bidirectional"))
    )
    (net (code "47") (name "Net-(U8A-VCAP_1)") (class "Default")
      (node (ref "C30") (pin "1") (pinfunction "1_1") (pintype "unspecified"))
      (node (ref "U8") (pin "31") (pinfunction "VCAP_1_31") (pintype "unspecified"))
    )
    (net (code "48") (name "Net-(U8A-VCAP_2)") (class "Default")
      (node (ref "C31") (pin "1") (pinfunction "1_1") (pintype "unspecified"))
      (node (ref "U8") (pin "47") (pinfunction "VCAP_2_47") (pintype "unspecified"))
    )
    (net (code "49") (name "unconnected-(SW2-Pad3)") (class "Default")
      (node (ref "SW2") (pin "3") (pinfunction "3_3") (pintype "unspecified+no_connect"))
    )
    (net (code "50") (name "unconnected-(SW2-Pad4)") (class "Default")
      (node (ref "SW2") (pin "4") (pinfunction "4_4") (pintype "unspecified+no_connect"))
    )
    (net (code "51") (name "unconnected-(SW2-Pad5)") (class "Default")
      (node (ref "SW2") (pin "5") (pinfunction "5_5") (pintype "unspecified+no_connect"))
    )
    (net (code "52") (name "unconnected-(U1-AUX_CL-Pad7)") (class "Default")
      (node (ref "U1") (pin "7") (pinfunction "AUX_CL_7") (pintype "unspecified+no_connect"))
    )
    (net (code "53") (name "unconnected-(U1-AUX_DA-Pad6)") (class "Default")
      (node (ref "U1") (pin "6") (pinfunction "AUX_DA_6") (pintype "unspecified+no_connect"))
    )
    (net (code "54") (name "unconnected-(U1-NC-Pad2)") (class "Default")
      (node (ref "U1") (pin "2") (pinfunction "NC_2") (pintype "unspecified+no_connect"))
    )
    (net (code "55") (name "unconnected-(U1-NC-Pad3)") (class "Default")
      (node (ref "U1") (pin "3") (pinfunction "NC_3") (pintype "unspecified+no_connect"))
    )
    (net (code "56") (name "unconnected-(U1-NC-Pad4)") (class "Default")
      (node (ref "U1") (pin "4") (pinfunction "NC_4") (pintype "unspecified+no_connect"))
    )
    (net (code "57") (name "unconnected-(U1-NC-Pad5)") (class "Default")
      (node (ref "U1") (pin "5") (pinfunction "NC_5") (pintype "unspecified+no_connect"))
    )
    (net (code "58") (name "unconnected-(U1-NC-Pad14)") (class "Default")
      (node (ref "U1") (pin "14") (pinfunction "NC_14") (pintype "unspecified+no_connect"))
    )
    (net (code "59") (name "unconnected-(U1-NC-Pad15)") (class "Default")
      (node (ref "U1") (pin "15") (pinfunction "NC_15") (pintype "unspecified+no_connect"))
    )
    (net (code "60") (name "unconnected-(U1-NC-Pad16)") (class "Default")
      (node (ref "U1") (pin "16") (pinfunction "NC_16") (pintype "unspecified+no_connect"))
    )
    (net (code "61") (name "unconnected-(U1-NC-Pad17)") (class "Default")
      (node (ref "U1") (pin "17") (pinfunction "NC_17") (pintype "unspecified+no_connect"))
    )
    (net (code "62") (name "unconnected-(U1-RESV-Pad19)") (class "Default")
      (node (ref "U1") (pin "19") (pinfunction "RESV_19") (pintype "unspecified+no_connect"))
    )
    (net (code "63") (name "unconnected-(U1-RESV-Pad21)") (class "Default")
      (node (ref "U1") (pin "21") (pinfunction "RESV_21") (pintype "unspecified+no_connect"))
    )
    (net (code "64") (name "unconnected-(U1-RESV-Pad22)") (class "Default")
      (node (ref "U1") (pin "22") (pinfunction "RESV_22") (pintype "unspecified+no_connect"))
    )
    (net (code "65") (name "unconnected-(U8A-NRST-Pad7)") (class "Default")
      (node (ref "U8") (pin "7") (pinfunction "NRST_7") (pintype "bidirectional+no_connect"))
    )
    (net (code "66") (name "unconnected-(U8A-PA2-Pad16)") (class "Default")
      (node (ref "U8") (pin "16") (pinfunction "PA2_16") (pintype "bidirectional+no_connect"))
    )
    (net (code "67") (name "unconnected-(U8A-PA3-Pad17)") (class "Default")
      (node (ref "U8") (pin "17") (pinfunction "PA3_17") (pintype "bidirectional+no_connect"))
    )
    (net (code "68") (name "unconnected-(U8A-PA4-Pad20)") (class "Default")
      (node (ref "U8") (pin "20") (pinfunction "PA4_20") (pintype "bidirectional+no_connect"))
    )
    (net (code "69") (name "unconnected-(U8A-PA5-Pad21)") (class "Default")
      (node (ref "U8") (pin "21") (pinfunction "PA5_21") (pintype "bidirectional+no_connect"))
    )
    (net (code "70") (name "unconnected-(U8A-PA6-Pad22)") (class "Default")
      (node (ref "U8") (pin "22") (pinfunction "PA6_22") (pintype "bidirectional+no_connect"))
    )
    (net (code "71") (name "unconnected-(U8A-PA11-Pad44)") (class "Default")
      (node (ref "U8") (pin "44") (pinfunction "PA11_44") (pintype "bidirectional+no_connect"))
    )
    (net (code "72") (name "unconnected-(U8A-PA12-Pad45)") (class "Default")
      (node (ref "U8") (pin "45") (pinfunction "PA12_45") (pintype "bidirectional+no_connect"))
    )
    (net (code "73") (name "unconnected-(U8A-PA15(JTDI)-Pad50)") (class "Default")
      (node (ref "U8") (pin "50") (pinfunction "PA15(JTDI)_50") (pintype "bidirectional+no_connect"))
    )
    (net (code "74") (name "unconnected-(U8A-PB1-Pad27)") (class "Default")
      (node (ref "U8") (pin "27") (pinfunction "PB1_27") (pintype "bidirectional+no_connect"))
    )
    (net (code "75") (name "unconnected-(U8A-PB2-BOOT1(PB2)-Pad28)") (class "Default")
      (node (ref "U8") (pin "28") (pinfunction "PB2-BOOT1(PB2)_28") (pintype "bidirectional+no_connect"))
    )
    (net (code "76") (name "unconnected-(U8A-PB4(NJTRST)-Pad56)") (class "Default")
      (node (ref "U8") (pin "56") (pinfunction "PB4(NJTRST)_56") (pintype "bidirectional+no_connect"))
    )
    (net (code "77") (name "unconnected-(U8A-PB5-Pad57)") (class "Default")
      (node (ref "U8") (pin "57") (pinfunction "PB5_57") (pintype "bidirectional+no_connect"))
    )
    (net (code "78") (name "unconnected-(U8A-PB7-Pad59)") (class "Default")
      (node (ref "U8") (pin "59") (pinfunction "PB7_59") (pintype "bidirectional+no_connect"))
    )
    (net (code "79") (name "unconnected-(U8A-PB8-Pad61)") (class "Default")
      (node (ref "U8") (pin "61") (pinfunction "PB8_61") (pintype "bidirectional+no_connect"))
    )
    (net (code "80") (name "unconnected-(U8A-PB9-Pad62)") (class "Default")
      (node (ref "U8") (pin "62") (pinfunction "PB9_62") (pintype "bidirectional+no_connect"))
    )
    (net (code "81") (name "unconnected-(U8A-PB10-Pad29)") (class "Default")
      (node (ref "U8") (pin "29") (pinfunction "PB10_29") (pintype "bidirectional+no_connect"))
    )
    (net (code "82") (name "unconnected-(U8A-PB11-Pad30)") (class "Default")
      (node (ref "U8") (pin "30") (pinfunction "PB11_30") (pintype "bidirectional+no_connect"))
    )
    (net (code "83") (name "unconnected-(U8A-PB12-Pad33)") (class "Default")
      (node (ref "U8") (pin "33") (pinfunction "PB12_33") (pintype "bidirectional+no_connect"))
    )
    (net (code "84") (name "unconnected-(U8A-PB14-Pad35)") (class "Default")
      (node (ref "U8") (pin "35") (pinfunction "PB14_35") (pintype "bidirectional+no_connect"))
    )
    (net (code "85") (name "unconnected-(U8A-PC0-Pad8)") (class "Default")
      (node (ref "U8") (pin "8") (pinfunction "PC0_8") (pintype "bidirectional+no_connect"))
    )
    (net (code "86") (name "unconnected-(U8A-PC4-Pad24)") (class "Default")
      (node (ref "U8") (pin "24") (pinfunction "PC4_24") (pintype "bidirectional+no_connect"))
    )
    (net (code "87") (name "unconnected-(U8A-PC5-Pad25)") (class "Default")
      (node (ref "U8") (pin "25") (pinfunction "PC5_25") (pintype "bidirectional+no_connect"))
    )
    (net (code "88") (name "unconnected-(U8A-PC6-Pad37)") (class "Default")
      (node (ref "U8") (pin "37") (pinfunction "PC6_37") (pintype "bidirectional+no_connect"))
    )
    (net (code "89") (name "unconnected-(U8A-PC7-Pad38)") (class "Default")
      (node (ref "U8") (pin "38") (pinfunction "PC7_38") (pintype "bidirectional+no_connect"))
    )
    (net (code "90") (name "unconnected-(U8A-PC10-Pad51)") (class "Default")
      (node (ref "U8") (pin "51") (pinfunction "PC10_51") (pintype "bidirectional+no_connect"))
    )
    (net (code "91") (name "unconnected-(U8A-PC11-Pad52)") (class "Default")
      (node (ref "U8") (pin "52") (pinfunction "PC11_52") (pintype "bidirectional+no_connect"))
    )
    (net (code "92") (name "unconnected-(U8A-PC12-Pad53)") (class "Default")
      (node (ref "U8") (pin "53") (pinfunction "PC12_53") (pintype "bidirectional+no_connect"))
    )
    (net (code "93") (name "unconnected-(U8A-PC13-Pad2)") (class "Default")
      (node (ref "U8") (pin "2") (pinfunction "PC13_2") (pintype "bidirectional+no_connect"))
    )
    (net (code "94") (name "unconnected-(U8A-PC14-OSC32_IN(PC14)-Pad3)") (class "Default")
      (node (ref "U8") (pin "3") (pinfunction "PC14-OSC32_IN(PC14)_3") (pintype "bidirectional+no_connect"))
    )
    (net (code "95") (name "unconnected-(U8A-PC15-OSC32_OUT(PC15)-Pad4)") (class "Default")
      (node (ref "U8") (pin "4") (pinfunction "PC15-OSC32_OUT(PC15)_4") (pintype "bidirectional+no_connect"))
    )
    (net (code "96") (name "unconnected-(U8A-PD2-Pad54)") (class "Default")
      (node (ref "U8") (pin "54") (pinfunction "PD2_54") (pintype "bidirectional+no_connect"))
    )
    (net (code "97") (name "unconnected-(U9-NC-Pad4)") (class "Default")
      (node (ref "U9") (pin "4") (pinfunction "NC_4") (pintype "unspecified+no_connect"))
    )
  )
)
